# Capstone_Signal_Conditioners_Subsystem_T.net
KiCad netlist of a schematic drawn in Altium Designer
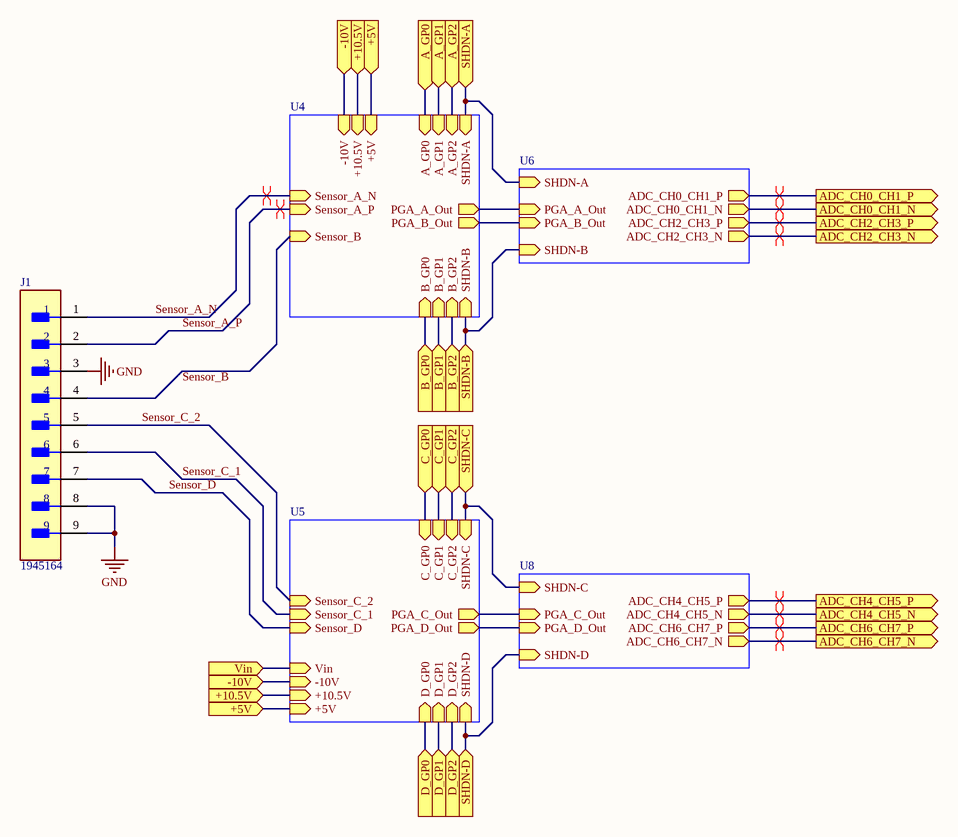
[diagram p0: Capstone_Signal_Conditioners_Subsystem_Test_Schematic.SchDoc]

(export (version "E")
  (design (tool "Eeschema 10.0.6"))
  (components
    (comp (ref "J1")
      (value "1945164")
      (footprint "1945164")
      (description "TERM BLOCK HDR 9POS VERT 3.5MM")
      (fields
        (field (name "OCTOPART") "https://octopart.com/4-644456-0-te+connectivity-39514173")
        (field (name "MANUFACTURER PART NUMBER") "4-644456-0")
      )
      (libsource (lib "Connectors") (part "1945164"))
    )
  )
  (nets
    (net (code "32") (name "/Sensor_A_N") (class "Default")
      (node (ref "J1") (pin "1") (pinfunction "1_1") (pintype "passive"))
    )
    (net (code "33") (name "/Sensor_A_P") (class "Default")
      (node (ref "J1") (pin "2") (pinfunction "2_2") (pintype "passive"))
    )
    (net (code "35") (name "/Sensor_B_1") (class "Default")
      (node (ref "J1") (pin "4") (pinfunction "4_4") (pintype "passive"))
    )
    (net (code "36") (name "/Sensor_C_1") (class "Default")
      (node (ref "J1") (pin "6") (pinfunction "6_6") (pintype "passive"))
    )
    (net (code "37") (name "/Sensor_C_2") (class "Default")
      (node (ref "J1") (pin "5") (pinfunction "5_5") (pintype "passive"))
    )
    (net (code "38") (name "/Sensor_D") (class "Default")
      (node (ref "J1") (pin "7") (pinfunction "7_7") (pintype "passive"))
    )
    (net (code "40") (name "GND") (class "Default")
      (node (ref "J1") (pin "3") (pinfunction "3_3") (pintype "passive"))
      (node (ref "J1") (pin "8") (pinfunction "8_8") (pintype "passive"))
      (node (ref "J1") (pin "9") (pinfunction "9_9") (pintype "passive"))
    )
  )
)
